# FlightLogger.net
KiCad netlist of a schematic drawn in Altium Designer
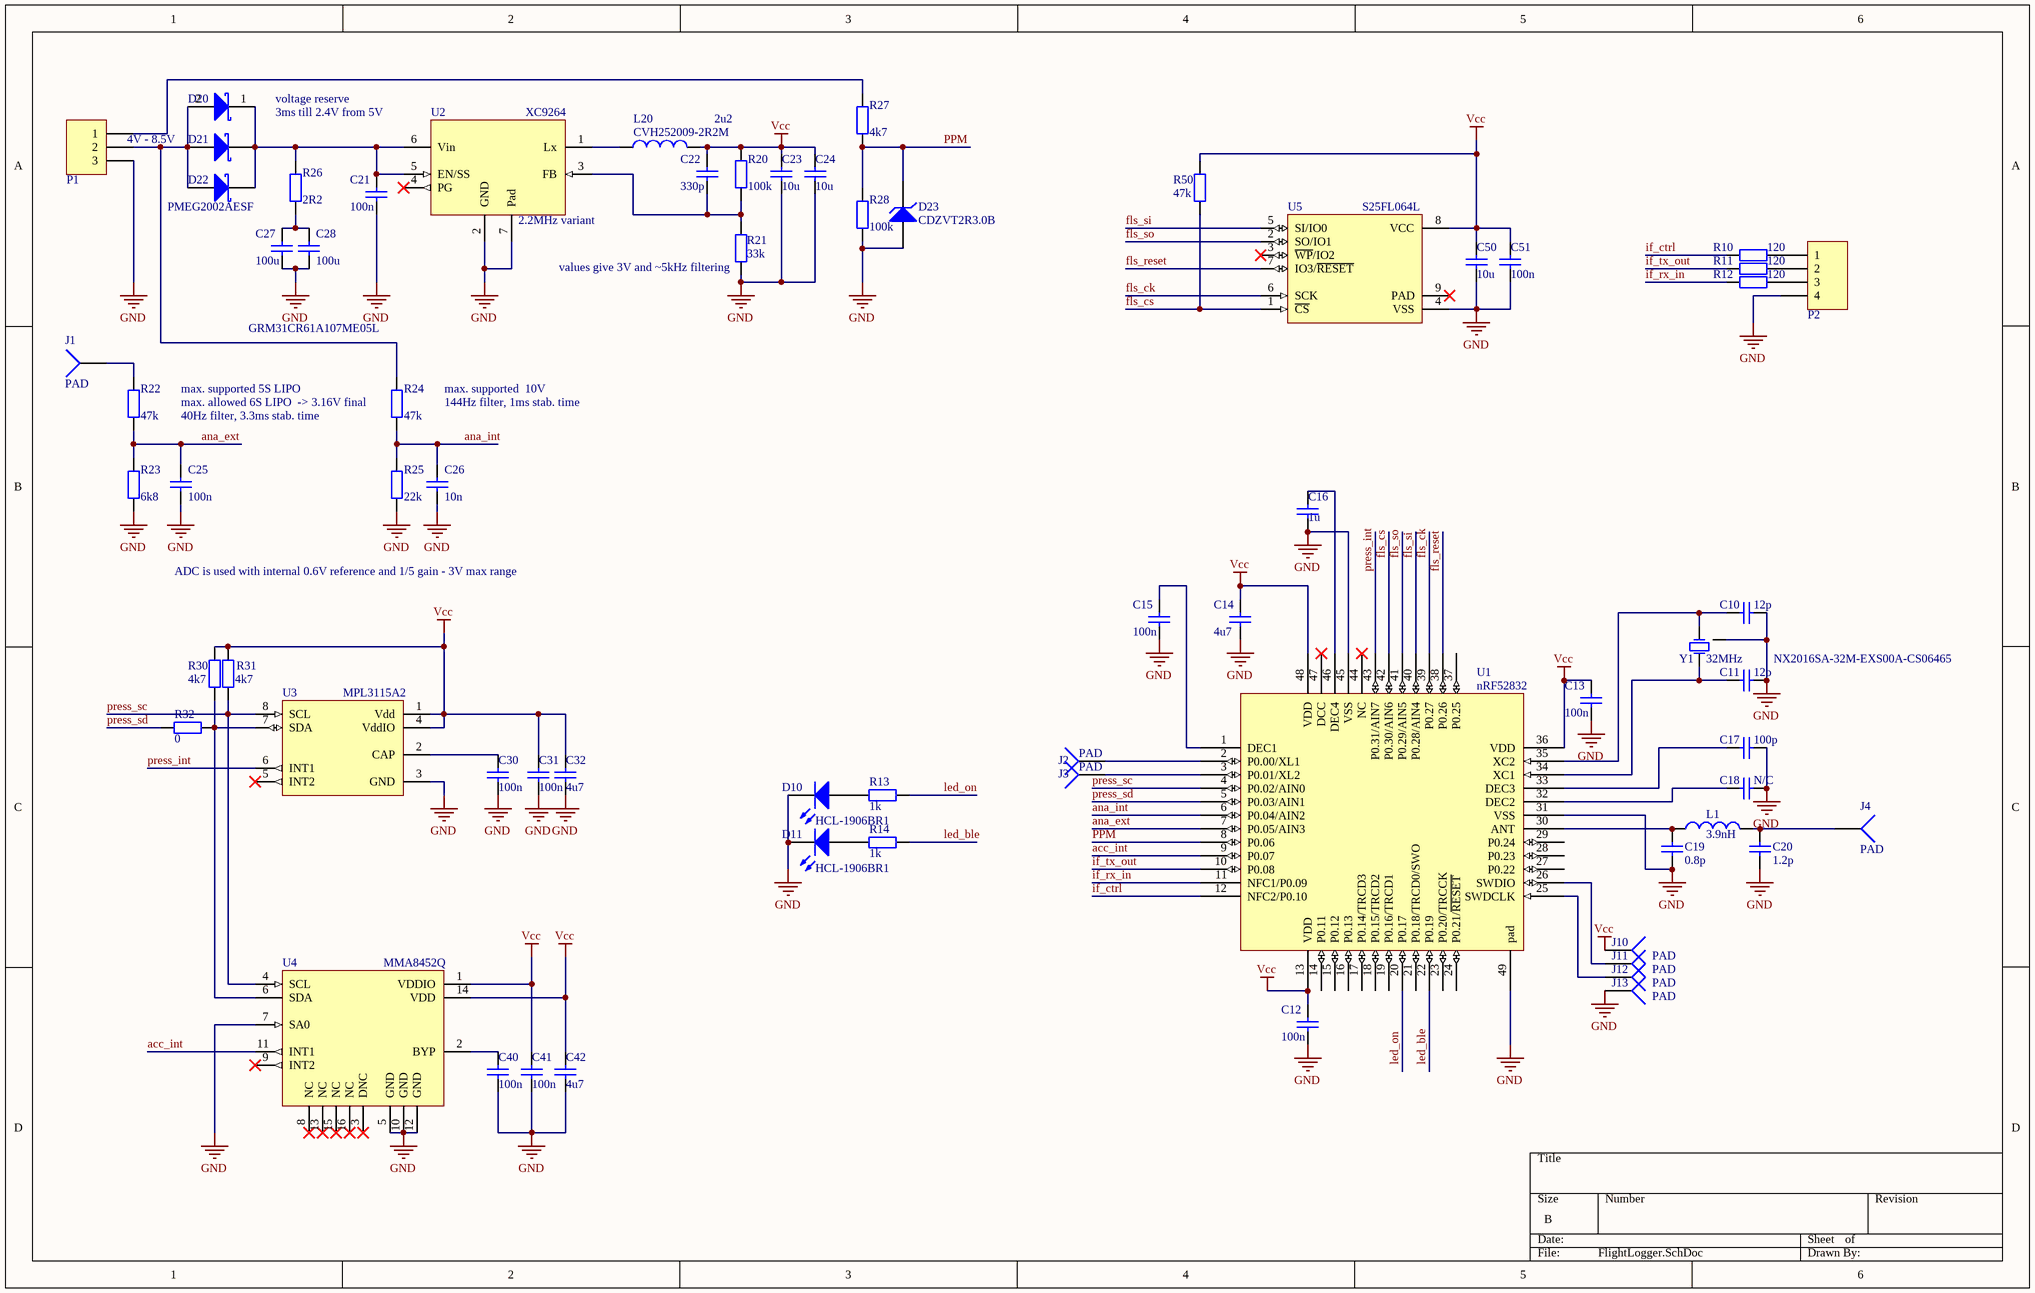
[diagram p0: FlightLogger.SchDoc]

(export (version "E")
  (design (tool "Eeschema 10.0.6"))
  (components
    (comp (ref "C10")
      (value "12p")
      (footprint "0402_cap")
      (description "Capacitor")
      (fields (field (name "PUBLISHER") "Altium Limited"))
      (libsource (lib "MyLib") (part "CAP"))
    )
    (comp (ref "C11")
      (value "12p")
      (footprint "0402_cap")
      (description "Capacitor")
      (fields (field (name "PUBLISHER") "Altium Limited"))
      (libsource (lib "MyLib") (part "CAP"))
    )
    (comp (ref "C12")
      (value "100n")
      (footprint "0402_cap")
      (description "Capacitor")
      (fields (field (name "PUBLISHER") "Altium Limited"))
      (libsource (lib "MyLib") (part "CAP"))
    )
    (comp (ref "C13")
      (value "100n")
      (footprint "0402_cap")
      (description "Capacitor")
      (fields (field (name "PUBLISHER") "Altium Limited"))
      (libsource (lib "MyLib") (part "CAP"))
    )
    (comp (ref "C14")
      (value "4u7")
      (footprint "0402_cap")
      (description "Capacitor")
      (fields (field (name "PUBLISHER") "Altium Limited"))
      (libsource (lib "MyLib") (part "CAP"))
    )
    (comp (ref "C15")
      (value "100n")
      (footprint "0402_cap")
      (description "Capacitor")
      (fields (field (name "PUBLISHER") "Altium Limited"))
      (libsource (lib "MyLib") (part "CAP"))
    )
    (comp (ref "C16")
      (value "1u")
      (footprint "0402_cap")
      (description "Capacitor")
      (fields (field (name "PUBLISHER") "Altium Limited"))
      (libsource (lib "MyLib") (part "CAP"))
    )
    (comp (ref "C17")
      (value "100p")
      (footprint "0402_cap")
      (description "Capacitor")
      (fields (field (name "PUBLISHER") "Altium Limited"))
      (libsource (lib "MyLib") (part "CAP"))
    )
    (comp (ref "C18")
      (value "N/C")
      (footprint "0402_cap")
      (description "Capacitor")
      (fields (field (name "PUBLISHER") "Altium Limited"))
      (libsource (lib "MyLib") (part "CAP"))
    )
    (comp (ref "C19")
      (value "0.8p")
      (footprint "0402_cap")
      (description "Capacitor")
      (fields (field (name "PUBLISHER") "Altium Limited"))
      (libsource (lib "MyLib") (part "CAP"))
    )
    (comp (ref "C20")
      (value "1.2p")
      (footprint "0402_cap")
      (description "Capacitor")
      (fields (field (name "PUBLISHER") "Altium Limited"))
      (libsource (lib "MyLib") (part "CAP"))
    )
    (comp (ref "C21")
      (value "100n")
      (footprint "0402_cap")
      (description "Capacitor")
      (fields (field (name "PUBLISHER") "Altium Limited"))
      (libsource (lib "MyLib") (part "CAP"))
    )
    (comp (ref "C22")
      (value "330p")
      (footprint "0402_cap")
      (description "Capacitor")
      (fields (field (name "PUBLISHER") "Altium Limited"))
      (libsource (lib "MyLib") (part "CAP"))
    )
    (comp (ref "C23")
      (value "10u")
      (footprint "0402_cap")
      (description "Capacitor")
      (fields (field (name "PUBLISHER") "Altium Limited"))
      (libsource (lib "MyLib") (part "CAP"))
    )
    (comp (ref "C24")
      (value "10u")
      (footprint "0402_cap")
      (description "Capacitor")
      (fields (field (name "PUBLISHER") "Altium Limited"))
      (libsource (lib "MyLib") (part "CAP"))
    )
    (comp (ref "C25")
      (value "100n")
      (footprint "0402_cap")
      (description "Capacitor")
      (fields (field (name "PUBLISHER") "Altium Limited"))
      (libsource (lib "MyLib") (part "CAP"))
    )
    (comp (ref "C26")
      (value "10n")
      (footprint "0402_cap")
      (description "Capacitor")
      (fields (field (name "PUBLISHER") "Altium Limited"))
      (libsource (lib "MyLib") (part "CAP"))
    )
    (comp (ref "C27")
      (value "100u")
      (footprint "1206_cap")
      (description "Capacitor")
      (fields (field (name "PARTNO") "GRM31CR61A107ME05L") (field (name "PUBLISHER") "Altium Limited"))
      (libsource (lib "MyLib") (part "CAP"))
    )
    (comp (ref "C28")
      (value "100u")
      (footprint "1206_cap")
      (description "Capacitor")
      (fields (field (name "PARTNO") "GRM31CR61A107ME05L") (field (name "PUBLISHER") "Altium Limited"))
      (libsource (lib "MyLib") (part "CAP"))
    )
    (comp (ref "C30")
      (value "100n")
      (footprint "0402_cap")
      (description "Capacitor")
      (fields (field (name "PUBLISHER") "Altium Limited"))
      (libsource (lib "MyLib") (part "CAP"))
    )
    (comp (ref "C31")
      (value "100n")
      (footprint "0402_cap")
      (description "Capacitor")
      (fields (field (name "PUBLISHER") "Altium Limited"))
      (libsource (lib "MyLib") (part "CAP"))
    )
    (comp (ref "C32")
      (value "4u7")
      (footprint "0402_cap")
      (description "Capacitor")
      (fields (field (name "PUBLISHER") "Altium Limited"))
      (libsource (lib "MyLib") (part "CAP"))
    )
    (comp (ref "C40")
      (value "100n")
      (footprint "0402_cap")
      (description "Capacitor")
      (fields (field (name "PUBLISHER") "Altium Limited"))
      (libsource (lib "MyLib") (part "CAP"))
    )
    (comp (ref "C41")
      (value "100n")
      (footprint "0402_cap")
      (description "Capacitor")
      (fields (field (name "PUBLISHER") "Altium Limited"))
      (libsource (lib "MyLib") (part "CAP"))
    )
    (comp (ref "C42")
      (value "4u7")
      (footprint "0402_cap")
      (description "Capacitor")
      (fields (field (name "PUBLISHER") "Altium Limited"))
      (libsource (lib "MyLib") (part "CAP"))
    )
    (comp (ref "C50")
      (value "10u")
      (footprint "0402_cap")
      (description "Capacitor")
      (fields (field (name "PUBLISHER") "Altium Limited"))
      (libsource (lib "MyLib") (part "CAP"))
    )
    (comp (ref "C51")
      (value "100n")
      (footprint "0402_cap")
      (description "Capacitor")
      (fields (field (name "PUBLISHER") "Altium Limited"))
      (libsource (lib "MyLib") (part "CAP"))
    )
    (comp (ref "D10")
      (value "HCL-1906BR1")
      (footprint "0603_led_green")
      (description "Typical RED, GREEN, YELLOW, AMBER GaAs LED")
      (fields (field (name "PUBLISHER") "Altium Limited"))
      (libsource (lib "MyLib") (part "LED"))
    )
    (comp (ref "D11")
      (value "HCL-1906BR1")
      (footprint "0603_led_green")
      (description "Typical RED, GREEN, YELLOW, AMBER GaAs LED")
      (fields (field (name "PUBLISHER") "Altium Limited"))
      (libsource (lib "MyLib") (part "LED"))
    )
    (comp (ref "D20")
      (value "PMEG2002AESF")
      (footprint "SOD962_2")
      (description "Schottky Barrier Diode")
      (fields (field (name "PUBLISHER") "Altium Limited"))
      (libsource (lib "") (part "1PS76SB10_1"))
    )
    (comp (ref "D21")
      (value "PMEG2002AESF")
      (footprint "SOD962_2")
      (description "Schottky Barrier Diode")
      (fields (field (name "PUBLISHER") "Altium Limited"))
      (libsource (lib "Philips Discrete Diode - Schottky") (part "1PS76SB10"))
    )
    (comp (ref "D22")
      (value "PMEG2002AESF")
      (footprint "SOD962_2")
      (description "Schottky Barrier Diode")
      (fields (field (name "PUBLISHER") "Altium Limited"))
      (libsource (lib "Philips Discrete Diode - Schottky") (part "1PS76SB10"))
    )
    (comp (ref "D23")
      (value "CDZVT2R3.0B")
      (footprint "VMN2M")
      (description "Zener Diode")
      (fields (field (name "PUBLISHER") "Altium Limited"))
      (libsource (lib "Miscellaneous Devices") (part "D Zener"))
    )
    (comp (ref "J1")
      (value "PAD")
      (footprint "PAD_0.6x1mm")
      (description "Pad")
      (fields (field (name "PUBLISHER") "Altium Limited"))
      (libsource (lib "MyLib") (part "PAD"))
    )
    (comp (ref "J2")
      (value "PAD")
      (footprint "PAD_0.6x1mm")
      (description "Pad")
      (fields (field (name "PUBLISHER") "Altium Limited"))
      (libsource (lib "MyLib") (part "PAD"))
    )
    (comp (ref "J3")
      (value "PAD")
      (footprint "PAD_0.6x1mm")
      (description "Pad")
      (fields (field (name "PUBLISHER") "Altium Limited"))
      (libsource (lib "MyLib") (part "PAD"))
    )
    (comp (ref "J4")
      (value "PAD")
      (footprint "PAD_0.6x1mm")
      (description "Pad")
      (fields (field (name "PUBLISHER") "Altium Limited"))
      (libsource (lib "MyLib") (part "PAD"))
    )
    (comp (ref "J10")
      (value "PAD")
      (footprint "PAD_0.6x1mm")
      (description "Pad")
      (fields (field (name "PUBLISHER") "Altium Limited"))
      (libsource (lib "MyLib") (part "PAD"))
    )
    (comp (ref "J11")
      (value "PAD")
      (footprint "PAD_0.6x1mm")
      (description "Pad")
      (fields (field (name "PUBLISHER") "Altium Limited"))
      (libsource (lib "MyLib") (part "PAD"))
    )
    (comp (ref "J12")
      (value "PAD")
      (footprint "PAD_0.6x1mm")
      (description "Pad")
      (fields (field (name "PUBLISHER") "Altium Limited"))
      (libsource (lib "MyLib") (part "PAD"))
    )
    (comp (ref "J13")
      (value "PAD")
      (footprint "PAD_0.6x1mm")
      (description "Pad")
      (fields (field (name "PUBLISHER") "Altium Limited"))
      (libsource (lib "MyLib") (part "PAD"))
    )
    (comp (ref "L1")
      (value "3.9nH")
      (footprint "0402_res")
      (description "Inductor")
      (fields (field (name "PUBLISHER") "Altium Limited"))
      (libsource (lib "MyLib") (part "Inductor"))
    )
    (comp (ref "L20")
      (value "CVH252009-2R2M")
      (footprint "1008_Inductor")
      (description "Inductor")
      (fields (field (name "ALTIUM_VALUE") "2u2") (field (name "PUBLISHER") "Altium Limited"))
      (libsource (lib "MyLib") (part "Inductor"))
    )
    (comp (ref "P1")
      (value "Conn3")
      (footprint "HDR1X3")
      (description "3pin connection")
      (fields (field (name "PUBLISHER") "Altium Limited"))
      (libsource (lib "MyLib") (part "conn_3pin_1"))
    )
    (comp (ref "P2")
      (value "Conn4")
      (footprint "conn_4pin_1row_1mm")
      (description "4pin connection")
      (fields (field (name "PUBLISHER") "Altium Limited"))
      (libsource (lib "MyLib") (part "conn_4pin"))
    )
    (comp (ref "R10")
      (value "120")
      (footprint "0402_res")
      (description "Resistor")
      (fields (field (name "PUBLISHER") "Altium Limited"))
      (libsource (lib "") (part "RES_1"))
    )
    (comp (ref "R11")
      (value "120")
      (footprint "0402_res")
      (description "Resistor")
      (fields (field (name "PUBLISHER") "Altium Limited"))
      (libsource (lib "") (part "RES_1"))
    )
    (comp (ref "R12")
      (value "120")
      (footprint "0402_res")
      (description "Resistor")
      (fields (field (name "PUBLISHER") "Altium Limited"))
      (libsource (lib "") (part "RES_1"))
    )
    (comp (ref "R13")
      (value "1k")
      (footprint "0402_res")
      (description "Resistor")
      (fields (field (name "PUBLISHER") "Altium Limited"))
      (libsource (lib "") (part "RES_1"))
    )
    (comp (ref "R14")
      (value "1k")
      (footprint "0402_res")
      (description "Resistor")
      (fields (field (name "PUBLISHER") "Altium Limited"))
      (libsource (lib "") (part "RES_1"))
    )
    (comp (ref "R20")
      (value "100k")
      (footprint "0402_res")
      (description "Resistor")
      (fields (field (name "PUBLISHER") "Altium Limited"))
      (libsource (lib "MyLib") (part "RES"))
    )
    (comp (ref "R21")
      (value "33k")
      (footprint "0402_res")
      (description "Resistor")
      (fields (field (name "PUBLISHER") "Altium Limited"))
      (libsource (lib "") (part "RES_2"))
    )
    (comp (ref "R22")
      (value "47k")
      (footprint "0402_res")
      (description "Resistor")
      (fields (field (name "PUBLISHER") "Altium Limited"))
      (libsource (lib "MyLib") (part "RES"))
    )
    (comp (ref "R23")
      (value "6k8")
      (footprint "0402_res")
      (description "Resistor")
      (fields (field (name "PUBLISHER") "Altium Limited"))
      (libsource (lib "MyLib") (part "RES"))
    )
    (comp (ref "R24")
      (value "47k")
      (footprint "0402_res")
      (description "Resistor")
      (fields (field (name "PUBLISHER") "Altium Limited"))
      (libsource (lib "MyLib") (part "RES"))
    )
    (comp (ref "R25")
      (value "22k")
      (footprint "0402_res")
      (description "Resistor")
      (fields (field (name "PUBLISHER") "Altium Limited"))
      (libsource (lib "MyLib") (part "RES"))
    )
    (comp (ref "R26")
      (value "2R2")
      (footprint "0603_res")
      (description "Resistor")
      (fields (field (name "PUBLISHER") "Altium Limited"))
      (libsource (lib "MyLib") (part "RES"))
    )
    (comp (ref "R27")
      (value "4k7")
      (footprint "0402_res")
      (description "Resistor")
      (fields (field (name "PUBLISHER") "Altium Limited"))
      (libsource (lib "MyLib") (part "RES"))
    )
    (comp (ref "R28")
      (value "100k")
      (footprint "0402_res")
      (description "Resistor")
      (fields (field (name "PUBLISHER") "Altium Limited"))
      (libsource (lib "MyLib") (part "RES"))
    )
    (comp (ref "R30")
      (value "4k7")
      (footprint "0402_res")
      (description "Resistor")
      (fields (field (name "PUBLISHER") "Altium Limited"))
      (libsource (lib "MyLib") (part "RES"))
    )
    (comp (ref "R31")
      (value "4k7")
      (footprint "0402_res")
      (description "Resistor")
      (fields (field (name "PUBLISHER") "Altium Limited"))
      (libsource (lib "MyLib") (part "RES"))
    )
    (comp (ref "R32")
      (value "0")
      (footprint "0402_res")
      (description "Resistor")
      (fields (field (name "PUBLISHER") "Altium Limited"))
      (libsource (lib "") (part "RES_1"))
    )
    (comp (ref "R50")
      (value "47k")
      (footprint "0402_res")
      (description "Resistor")
      (fields (field (name "PUBLISHER") "Altium Limited"))
      (libsource (lib "MyLib") (part "RES"))
    )
    (comp (ref "U1")
      (value "nRF52832")
      (footprint "QFN48")
      (description "ARM Cortex M4  microcontroller with 2.4GHz radio")
      (libsource (lib "MyLib") (part "nRF52832"))
    )
    (comp (ref "U2")
      (value "XC9264")
      (footprint "USP-6C")
      (description "18V 0.5A step down DC-DC converter")
      (libsource (lib "MyLib") (part "XC9264"))
    )
    (comp (ref "U3")
      (value "MPL3115A2")
      (footprint "MPL3115A2")
      (description "Precision barometer sensor I2C")
      (fields (field (name "PUBLISHER") "Altium Limited"))
      (libsource (lib "MyLib") (part "MPL3115A2"))
    )
    (comp (ref "U4")
      (value "MMA8452Q")
      (footprint "QFN16SP")
      (description "3 axis accelerometer")
      (fields (field (name "PUBLISHER") "Altium Limited"))
      (libsource (lib "MyLib") (part "MMA8452Q"))
    )
    (comp (ref "U5")
      (value "S25FL064L")
      (footprint "USON8")
      (description "64Mbit NOR flash")
      (fields (field (name "PUBLISHER") "Altium Limited"))
      (libsource (lib "MyLib") (part "S25FL064L"))
    )
    (comp (ref "Y1")
      (value "32MHz")
      (footprint "Cristal_2_1.6_4pin")
      (description "Crystal Oscillator")
      (fields
        (field (name "PART.NO") "NX2016SA-32M-EXS00A-CS06465")
        (field (name "PUBLISHER") "Altium Limited")
      )
      (libsource (lib "MyLib") (part "XTAL"))
    )
  )
  (nets
    (net (code "1") (name "/PPM") (class "Default")
      (node (ref "D23") (pin "2") (pinfunction "K_2") (pintype "passive"))
      (node (ref "R27") (pin "2") (pinfunction "2_2") (pintype "passive"))
      (node (ref "R28") (pin "1") (pinfunction "1_1") (pintype "passive"))
      (node (ref "U1") (pin "8") (pinfunction "P0.06_8") (pintype "bidirectional"))
    )
    (net (code "2") (name "/acc_int") (class "Default")
      (node (ref "U1") (pin "9") (pinfunction "P0.07_9") (pintype "bidirectional"))
      (node (ref "U4") (pin "11") (pinfunction "INT1_11") (pintype "output"))
    )
    (net (code "3") (name "/ana_ext") (class "Default")
      (node (ref "C25") (pin "1") (pinfunction "1_1") (pintype "passive"))
      (node (ref "R22") (pin "2") (pinfunction "2_2") (pintype "passive"))
      (node (ref "R23") (pin "1") (pinfunction "1_1") (pintype "passive"))
      (node (ref "U1") (pin "7") (pinfunction "P0.05/AIN3_7") (pintype "bidirectional"))
    )
    (net (code "4") (name "/ana_int") (class "Default")
      (node (ref "C26") (pin "1") (pinfunction "1_1") (pintype "passive"))
      (node (ref "R24") (pin "2") (pinfunction "2_2") (pintype "passive"))
      (node (ref "R25") (pin "1") (pinfunction "1_1") (pintype "passive"))
      (node (ref "U1") (pin "6") (pinfunction "P0.04/AIN2_6") (pintype "bidirectional"))
    )
    (net (code "5") (name "/fls_ck") (class "Default")
      (node (ref "U1") (pin "39") (pinfunction "P0.27_39") (pintype "bidirectional"))
      (node (ref "U5") (pin "6") (pinfunction "SCK_6") (pintype "input"))
    )
    (net (code "6") (name "/fls_cs") (class "Default")
      (node (ref "R50") (pin "2") (pinfunction "2_2") (pintype "passive"))
      (node (ref "U1") (pin "42") (pinfunction "P0.30/AIN6_42") (pintype "bidirectional"))
      (node (ref "U5") (pin "1") (pinfunction "~{CS}_1") (pintype "input"))
    )
    (net (code "7") (name "/fls_reset") (class "Default")
      (node (ref "U1") (pin "38") (pinfunction "P0.26_38") (pintype "bidirectional"))
      (node (ref "U5") (pin "7") (pinfunction "IO3/~{RESET}_7") (pintype "bidirectional"))
    )
    (net (code "8") (name "/fls_si") (class "Default")
      (node (ref "U1") (pin "40") (pinfunction "P0.28/AIN4_40") (pintype "bidirectional"))
      (node (ref "U5") (pin "5") (pinfunction "SI/IO0_5") (pintype "bidirectional"))
    )
    (net (code "9") (name "/fls_so") (class "Default")
      (node (ref "U1") (pin "41") (pinfunction "P0.29/AIN5_41") (pintype "bidirectional"))
      (node (ref "U5") (pin "2") (pinfunction "SO/IO1_2") (pintype "bidirectional"))
    )
    (net (code "10") (name "/if_ctrl") (class "Default")
      (node (ref "R10") (pin "2") (pinfunction "2_2") (pintype "passive"))
      (node (ref "U1") (pin "12") (pinfunction "NFC2/P0.10_12") (pintype "tri_state"))
    )
    (net (code "11") (name "/if_rx_in") (class "Default")
      (node (ref "R12") (pin "2") (pinfunction "2_2") (pintype "passive"))
      (node (ref "U1") (pin "11") (pinfunction "NFC1/P0.09_11") (pintype "tri_state"))
    )
    (net (code "12") (name "/if_tx_out") (class "Default")
      (node (ref "R11") (pin "2") (pinfunction "2_2") (pintype "passive"))
      (node (ref "U1") (pin "10") (pinfunction "P0.08_10") (pintype "bidirectional"))
    )
    (net (code "13") (name "/led_ble") (class "Default")
      (node (ref "R14") (pin "1") (pinfunction "1_1") (pintype "passive"))
      (node (ref "U1") (pin "22") (pinfunction "P0.19_22") (pintype "bidirectional"))
    )
    (net (code "14") (name "/led_on") (class "Default")
      (node (ref "R13") (pin "1") (pinfunction "1_1") (pintype "passive"))
      (node (ref "U1") (pin "20") (pinfunction "P0.17_20") (pintype "bidirectional"))
    )
    (net (code "15") (name "/press_int") (class "Default")
      (node (ref "U1") (pin "43") (pinfunction "P0.31/AIN7_43") (pintype "bidirectional"))
      (node (ref "U3") (pin "6") (pinfunction "INT1_6") (pintype "output"))
    )
    (net (code "16") (name "/press_sc") (class "Default")
      (node (ref "R31") (pin "2") (pinfunction "2_2") (pintype "passive"))
      (node (ref "U1") (pin "4") (pinfunction "P0.02/AIN0_4") (pintype "bidirectional"))
      (node (ref "U3") (pin "8") (pinfunction "SCL_8") (pintype "input"))
      (node (ref "U4") (pin "4") (pinfunction "SCL_4") (pintype "input"))
    )
    (net (code "17") (name "/press_sd") (class "Default")
      (node (ref "R32") (pin "2") (pinfunction "2_2") (pintype "passive"))
      (node (ref "U1") (pin "5") (pinfunction "P0.03/AIN1_5") (pintype "bidirectional"))
    )
    (net (code "18") (name "GND") (class "Default")
      (node (ref "C10") (pin "1") (pinfunction "1_1") (pintype "passive"))
      (node (ref "C11") (pin "1") (pinfunction "1_1") (pintype "passive"))
      (node (ref "C12") (pin "2") (pinfunction "2_2") (pintype "passive"))
      (node (ref "C13") (pin "2") (pinfunction "2_2") (pintype "passive"))
      (node (ref "C14") (pin "2") (pinfunction "2_2") (pintype "passive"))
      (node (ref "C15") (pin "2") (pinfunction "2_2") (pintype "passive"))
      (node (ref "C16") (pin "2") (pinfunction "2_2") (pintype "passive"))
      (node (ref "C17") (pin "1") (pinfunction "1_1") (pintype "passive"))
      (node (ref "C18") (pin "1") (pinfunction "1_1") (pintype "passive"))
      (node (ref "C19") (pin "1") (pinfunction "1_1") (pintype "passive"))
      (node (ref "C20") (pin "1") (pinfunction "1_1") (pintype "passive"))
      (node (ref "C21") (pin "2") (pinfunction "2_2") (pintype "passive"))
      (node (ref "C23") (pin "2") (pinfunction "2_2") (pintype "passive"))
      (node (ref "C24") (pin "2") (pinfunction "2_2") (pintype "passive"))
      (node (ref "C25") (pin "2") (pinfunction "2_2") (pintype "passive"))
      (node (ref "C26") (pin "2") (pinfunction "2_2") (pintype "passive"))
      (node (ref "C27") (pin "1") (pinfunction "1_1") (pintype "passive"))
      (node (ref "C28") (pin "1") (pinfunction "1_1") (pintype "passive"))
      (node (ref "C30") (pin "1") (pinfunction "1_1") (pintype "passive"))
      (node (ref "C31") (pin "1") (pinfunction "1_1") (pintype "passive"))
      (node (ref "C32") (pin "1") (pinfunction "1_1") (pintype "passive"))
      (node (ref "C40") (pin "1") (pinfunction "1_1") (pintype "passive"))
      (node (ref "C41") (pin "1") (pinfunction "1_1") (pintype "passive"))
      (node (ref "C42") (pin "1") (pinfunction "1_1") (pintype "passive"))
      (node (ref "C50") (pin "1") (pinfunction "1_1") (pintype "passive"))
      (node (ref "C51") (pin "1") (pinfunction "1_1") (pintype "passive"))
      (node (ref "D10") (pin "2") (pinfunction "K_2") (pintype "passive"))
      (node (ref "D11") (pin "2") (pinfunction "K_2") (pintype "passive"))
      (node (ref "D23") (pin "1") (pinfunction "A_1") (pintype "passive"))
      (node (ref "J13") (pin "1") (pinfunction "1_1") (pintype "passive"))
      (node (ref "P1") (pin "3") (pinfunction "3_3") (pintype "passive"))
      (node (ref "P2") (pin "4") (pinfunction "4_4") (pintype "passive"))
      (node (ref "R21") (pin "1") (pinfunction "1_1") (pintype "passive"))
      (node (ref "R23") (pin "2") (pinfunction "2_2") (pintype "passive"))
      (node (ref "R25") (pin "2") (pinfunction "2_2") (pintype "passive"))
      (node (ref "R28") (pin "2") (pinfunction "2_2") (pintype "passive"))
      (node (ref "U1") (pin "31") (pinfunction "VSS_31") (pintype "power_in"))
      (node (ref "U1") (pin "45") (pinfunction "VSS_45") (pintype "power_in"))
      (node (ref "U1") (pin "49") (pinfunction "pad_49") (pintype "power_in"))
      (node (ref "U2") (pin "2") (pinfunction "GND_2") (pintype "power_in"))
      (node (ref "U2") (pin "7") (pinfunction "Pad_7") (pintype "passive"))
      (node (ref "U3") (pin "3") (pinfunction "GND_3") (pintype "power_in"))
      (node (ref "U4") (pin "10") (pinfunction "GND_10") (pintype "power_in"))
      (node (ref "U4") (pin "12") (pinfunction "GND_12") (pintype "power_in"))
      (node (ref "U4") (pin "5") (pinfunction "GND_5") (pintype "power_in"))
      (node (ref "U4") (pin "7") (pinfunction "SA0_7") (pintype "input"))
      (node (ref "U5") (pin "4") (pinfunction "VSS_4") (pintype "power_in"))
      (node (ref "Y1") (pin "2") (pinfunction "GND_2") (pintype "passive"))
    )
    (net (code "19") (name "Net-(C20-Pad2)") (class "Default")
      (node (ref "C20") (pin "2") (pinfunction "2_2") (pintype "passive"))
      (node (ref "J4") (pin "1") (pinfunction "1_1") (pintype "passive"))
      (node (ref "L1") (pin "2") (pinfunction "2_2") (pintype "passive"))
    )
    (net (code "20") (name "Net-(C27-Pad2)") (class "Default")
      (node (ref "C27") (pin "2") (pinfunction "2_2") (pintype "passive"))
      (node (ref "C28") (pin "2") (pinfunction "2_2") (pintype "passive"))
      (node (ref "R26") (pin "2") (pinfunction "2_2") (pintype "passive"))
    )
    (net (code "21") (name "Net-(D10-A)") (class "Default")
      (node (ref "D10") (pin "1") (pinfunction "A_1") (pintype "passive"))
      (node (ref "R13") (pin "2") (pinfunction "2_2") (pintype "passive"))
    )
    (net (code "22") (name "Net-(D11-A)") (class "Default")
      (node (ref "D11") (pin "1") (pinfunction "A_1") (pintype "passive"))
      (node (ref "R14") (pin "2") (pinfunction "2_2") (pintype "passive"))
    )
    (net (code "23") (name "Net-(D20-A)") (class "Default")
      (node (ref "D20") (pin "2") (pinfunction "A_2") (pintype "passive"))
      (node (ref "D21") (pin "2") (pinfunction "A_2") (pintype "passive"))
      (node (ref "D22") (pin "2") (pinfunction "A_2") (pintype "passive"))
      (node (ref "P1") (pin "2") (pinfunction "2_2") (pintype "passive"))
      (node (ref "R24") (pin "1") (pinfunction "1_1") (pintype "passive"))
    )
    (net (code "24") (name "Net-(D20-K)") (class "Default")
      (node (ref "C21") (pin "1") (pinfunction "1_1") (pintype "passive"))
      (node (ref "D20") (pin "1") (pinfunction "K_1") (pintype "passive"))
      (node (ref "D21") (pin "1") (pinfunction "K_1") (pintype "passive"))
      (node (ref "D22") (pin "1") (pinfunction "K_1") (pintype "passive"))
      (node (ref "R26") (pin "1") (pinfunction "1_1") (pintype "passive"))
      (node (ref "U2") (pin "5") (pinfunction "EN/SS_5") (pintype "input"))
      (node (ref "U2") (pin "6") (pinfunction "Vin_6") (pintype "power_in"))
    )
    (net (code "25") (name "Net-(J1-Pad1)") (class "Default")
      (node (ref "J1") (pin "1") (pinfunction "1_1") (pintype "passive"))
      (node (ref "R22") (pin "1") (pinfunction "1_1") (pintype "passive"))
    )
    (net (code "26") (name "Net-(P1-Pad1)") (class "Default")
      (node (ref "P1") (pin "1") (pinfunction "1_1") (pintype "passive"))
      (node (ref "R27") (pin "1") (pinfunction "1_1") (pintype "passive"))
    )
    (net (code "27") (name "Net-(P2-Pad1)") (class "Default")
      (node (ref "P2") (pin "1") (pinfunction "1_1") (pintype "passive"))
      (node (ref "R10") (pin "1") (pinfunction "1_1") (pintype "passive"))
    )
    (net (code "28") (name "Net-(P2-Pad2)") (class "Default")
      (node (ref "P2") (pin "2") (pinfunction "2_2") (pintype "passive"))
      (node (ref "R11") (pin "1") (pinfunction "1_1") (pintype "passive"))
    )
    (net (code "29") (name "Net-(P2-Pad3)") (class "Default")
      (node (ref "P2") (pin "3") (pinfunction "3_3") (pintype "passive"))
      (node (ref "R12") (pin "1") (pinfunction "1_1") (pintype "passive"))
    )
    (net (code "30") (name "Net-(U1-ANT)") (class "Default")
      (node (ref "C19") (pin "2") (pinfunction "2_2") (pintype "passive"))
      (node (ref "L1") (pin "1") (pinfunction "1_1") (pintype "passive"))
      (node (ref "U1") (pin "30") (pinfunction "ANT_30") (pintype "tri_state"))
    )
    (net (code "31") (name "Net-(U1-DEC1)") (class "Default")
      (node (ref "C15") (pin "1") (pinfunction "1_1") (pintype "passive"))
      (node (ref "U1") (pin "1") (pinfunction "DEC1_1") (pintype "power_in"))
    )
    (net (code "32") (name "Net-(U1-DEC2)") (class "Default")
      (node (ref "C18") (pin "2") (pinfunction "2_2") (pintype "passive"))
      (node (ref "U1") (pin "32") (pinfunction "DEC2_32") (pintype "power_in"))
    )
    (net (code "33") (name "Net-(U1-DEC3)") (class "Default")
      (node (ref "C17") (pin "2") (pinfunction "2_2") (pintype "passive"))
      (node (ref "U1") (pin "33") (pinfunction "DEC3_33") (pintype "power_in"))
    )
    (net (code "34") (name "Net-(U1-DEC4)") (class "Default")
      (node (ref "C16") (pin "1") (pinfunction "1_1") (pintype "passive"))
      (node (ref "U1") (pin "46") (pinfunction "DEC4_46") (pintype "power_in"))
    )
    (net (code "35") (name "Net-(U1-P0.00{slash}XL1)") (class "Default")
      (node (ref "J2") (pin "1") (pinfunction "1_1") (pintype "passive"))
      (node (ref "U1") (pin "2") (pinfunction "P0.00/XL1_2") (pintype "bidirectional"))
    )
    (net (code "36") (name "Net-(U1-P0.01{slash}XL2)") (class "Default")
      (node (ref "J3") (pin "1") (pinfunction "1_1") (pintype "passive"))
      (node (ref "U1") (pin "3") (pinfunction "P0.01/XL2_3") (pintype "bidirectional"))
    )
    (net (code "37") (name "Net-(U1-SWDCLK)") (class "Default")
      (node (ref "J12") (pin "1") (pinfunction "1_1") (pintype "passive"))
      (node (ref "U1") (pin "25") (pinfunction "SWDCLK_25") (pintype "input"))
    )
    (net (code "38") (name "Net-(U1-SWDIO)") (class "Default")
      (node (ref "J11") (pin "1") (pinfunction "1_1") (pintype "passive"))
      (node (ref "U1") (pin "26") (pinfunction "SWDIO_26") (pintype "bidirectional"))
    )
    (net (code "39") (name "Net-(U1-XC1)") (class "Default")
      (node (ref "C11") (pin "2") (pinfunction "2_2") (pintype "passive"))
      (node (ref "U1") (pin "34") (pinfunction "XC1_34") (pintype "input"))
      (node (ref "Y1") (pin "3") (pinfunction "OSC2_3") (pintype "passive"))
    )
    (net (code "40") (name "Net-(U1-XC2)") (class "Default")
      (node (ref "C10") (pin "2") (pinfunction "2_2") (pintype "passive"))
      (node (ref "U1") (pin "35") (pinfunction "XC2_35") (pintype "input"))
      (node (ref "Y1") (pin "1") (pinfunction "OSC1_1") (pintype "passive"))
    )
    (net (code "41") (name "Net-(U2-FB)") (class "Default")
      (node (ref "C22") (pin "2") (pinfunction "2_2") (pintype "passive"))
      (node (ref "R20") (pin "2") (pinfunction "2_2") (pintype "passive"))
      (node (ref "R21") (pin "2") (pinfunction "2_2") (pintype "passive"))
      (node (ref "U2") (pin "3") (pinfunction "FB_3") (pintype "input"))
    )
    (net (code "42") (name "Net-(U2-Lx)") (class "Default")
      (node (ref "L20") (pin "1") (pinfunction "1_1") (pintype "passive"))
      (node (ref "U2") (pin "1") (pinfunction "Lx_1") (pintype "power_in"))
    )
    (net (code "43") (name "Net-(U3-CAP)") (class "Default")
      (node (ref "C30") (pin "2") (pinfunction "2_2") (pintype "passive"))
      (node (ref "U3") (pin "2") (pinfunction "CAP_2") (pintype "passive"))
    )
    (net (code "44") (name "Net-(U3-SDA)") (class "Default")
      (node (ref "R30") (pin "2") (pinfunction "2_2") (pintype "passive"))
      (node (ref "R32") (pin "1") (pinfunction "1_1") (pintype "passive"))
      (node (ref "U3") (pin "7") (pinfunction "SDA_7") (pintype "bidirectional"))
      (node (ref "U4") (pin "6") (pinfunction "SDA_6") (pintype "open_collector"))
    )
    (net (code "45") (name "Net-(U4-BYP)") (class "Default")
      (node (ref "C40") (pin "2") (pinfunction "2_2") (pintype "passive"))
      (node (ref "U4") (pin "2") (pinfunction "BYP_2") (pintype "passive"))
    )
    (net (code "46") (name "Vcc") (class "Default")
      (node (ref "C12") (pin "1") (pinfunction "1_1") (pintype "passive"))
      (node (ref "C13") (pin "1") (pinfunction "1_1") (pintype "passive"))
      (node (ref "C14") (pin "1") (pinfunction "1_1") (pintype "passive"))
      (node (ref "C22") (pin "1") (pinfunction "1_1") (pintype "passive"))
      (node (ref "C23") (pin "1") (pinfunction "1_1") (pintype "passive"))
      (node (ref "C24") (pin "1") (pinfunction "1_1") (pintype "passive"))
      (node (ref "C31") (pin "2") (pinfunction "2_2") (pintype "passive"))
      (node (ref "C32") (pin "2") (pinfunction "2_2") (pintype "passive"))
      (node (ref "C41") (pin "2") (pinfunction "2_2") (pintype "passive"))
      (node (ref "C42") (pin "2") (pinfunction "2_2") (pintype "passive"))
      (node (ref "C50") (pin "2") (pinfunction "2_2") (pintype "passive"))
      (node (ref "C51") (pin "2") (pinfunction "2_2") (pintype "passive"))
      (node (ref "J10") (pin "1") (pinfunction "1_1") (pintype "passive"))
      (node (ref "L20") (pin "2") (pinfunction "2_2") (pintype "passive"))
      (node (ref "R20") (pin "1") (pinfunction "1_1") (pintype "passive"))
      (node (ref "R30") (pin "1") (pinfunction "1_1") (pintype "passive"))
      (node (ref "R31") (pin "1") (pinfunction "1_1") (pintype "passive"))
      (node (ref "R50") (pin "1") (pinfunction "1_1") (pintype "passive"))
      (node (ref "U1") (pin "13") (pinfunction "VDD_13") (pintype "power_in"))
      (node (ref "U1") (pin "36") (pinfunction "VDD_36") (pintype "power_in"))
      (node (ref "U1") (pin "48") (pinfunction "VDD_48") (pintype "power_in"))
      (node (ref "U3") (pin "1") (pinfunction "Vdd_1") (pintype "power_in"))
      (node (ref "U3") (pin "4") (pinfunction "VddIO_4") (pintype "power_in"))
      (node (ref "U4") (pin "1") (pinfunction "VDDIO_1") (pintype "power_in"))
      (node (ref "U4") (pin "14") (pinfunction "VDD_14") (pintype "power_in"))
      (node (ref "U5") (pin "8") (pinfunction "VCC_8") (pintype "power_in"))
    )
    (net (code "47") (name "unconnected-(U1-DCC-Pad47)") (class "Default")
      (node (ref "U1") (pin "47") (pinfunction "DCC_47") (pintype "power_in+no_connect"))
    )
    (net (code "48") (name "unconnected-(U1-NC-Pad44)") (class "Default")
      (node (ref "U1") (pin "44") (pinfunction "NC_44") (pintype "passive+no_connect"))
    )
    (net (code "49") (name "unconnected-(U1-P0.11-Pad14)") (class "Default")
      (node (ref "U1") (pin "14") (pinfunction "P0.11_14") (pintype "bidirectional"))
    )
    (net (code "50") (name "unconnected-(U1-P0.12-Pad15)") (class "Default")
      (node (ref "U1") (pin "15") (pinfunction "P0.12_15") (pintype "bidirectional"))
    )
    (net (code "51") (name "unconnected-(U1-P0.13-Pad16)") (class "Default")
      (node (ref "U1") (pin "16") (pinfunction "P0.13_16") (pintype "bidirectional"))
    )
    (net (code "52") (name "unconnected-(U1-P0.14{slash}TRCD3-Pad17)") (class "Default")
      (node (ref "U1") (pin "17") (pinfunction "P0.14/TRCD3_17") (pintype "bidirectional"))
    )
    (net (code "53") (name "unconnected-(U1-P0.15{slash}TRCD2-Pad18)") (class "Default")
      (node (ref "U1") (pin "18") (pinfunction "P0.15/TRCD2_18") (pintype "bidirectional"))
    )
    (net (code "54") (name "unconnected-(U1-P0.16{slash}TRCD1-Pad19)") (class "Default")
      (node (ref "U1") (pin "19") (pinfunction "P0.16/TRCD1_19") (pintype "bidirectional"))
    )
    (net (code "55") (name "unconnected-(U1-P0.18{slash}TRCD0{slash}SWO-Pad21)") (class "Default")
      (node (ref "U1") (pin "21") (pinfunction "P0.18/TRCD0/SWO_21") (pintype "bidirectional"))
    )
    (net (code "56") (name "unconnected-(U1-P0.20{slash}TRCCK-Pad23)") (class "Default")
      (node (ref "U1") (pin "23") (pinfunction "P0.20/TRCCK_23") (pintype "bidirectional"))
    )
    (net (code "57") (name "unconnected-(U1-P0.21{slash}~{RESET}-Pad24)") (class "Default")
      (node (ref "U1") (pin "24") (pinfunction "P0.21/~{RESET}_24") (pintype "bidirectional"))
    )
    (net (code "58") (name "unconnected-(U1-P0.22-Pad27)") (class "Default")
      (node (ref "U1") (pin "27") (pinfunction "P0.22_27") (pintype "bidirectional"))
    )
    (net (code "59") (name "unconnected-(U1-P0.23-Pad28)") (class "Default")
      (node (ref "U1") (pin "28") (pinfunction "P0.23_28") (pintype "bidirectional"))
    )
    (net (code "60") (name "unconnected-(U1-P0.24-Pad29)") (class "Default")
      (node (ref "U1") (pin "29") (pinfunction "P0.24_29") (pintype "bidirectional"))
    )
    (net (code "61") (name "unconnected-(U1-P0.25-Pad37)") (class "Default")
      (node (ref "U1") (pin "37") (pinfunction "P0.25_37") (pintype "bidirectional"))
    )
    (net (code "62") (name "unconnected-(U2-PG-Pad4)") (class "Default")
      (node (ref "U2") (pin "4") (pinfunction "PG_4") (pintype "output+no_connect"))
    )
    (net (code "63") (name "unconnected-(U3-INT2-Pad5)") (class "Default")
      (node (ref "U3") (pin "5") (pinfunction "INT2_5") (pintype "output+no_connect"))
    )
    (net (code "64") (name "unconnected-(U4-DNC-Pad3)") (class "Default")
      (node (ref "U4") (pin "3") (pinfunction "DNC_3") (pintype "passive+no_connect"))
    )
    (net (code "65") (name "unconnected-(U4-INT2-Pad9)") (class "Default")
      (node (ref "U4") (pin "9") (pinfunction "INT2_9") (pintype "output+no_connect"))
    )
    (net (code "66") (name "unconnected-(U4-NC-Pad8)") (class "Default")
      (node (ref "U4") (pin "8") (pinfunction "NC_8") (pintype "passive+no_connect"))
    )
    (net (code "67") (name "unconnected-(U4-NC-Pad13)") (class "Default")
      (node (ref "U4") (pin "13") (pinfunction "NC_13") (pintype "passive+no_connect"))
    )
    (net (code "68") (name "unconnected-(U4-NC-Pad15)") (class "Default")
      (node (ref "U4") (pin "15") (pinfunction "NC_15") (pintype "passive+no_connect"))
    )
    (net (code "69") (name "unconnected-(U4-NC-Pad16)") (class "Default")
      (node (ref "U4") (pin "16") (pinfunction "NC_16") (pintype "passive+no_connect"))
    )
    (net (code "70") (name "unconnected-(U5-PAD-Pad9)") (class "Default")
      (node (ref "U5") (pin "9") (pinfunction "PAD_9") (pintype "passive+no_connect"))
    )
    (net (code "71") (name "unconnected-(U5-~{WP}{slash}IO2-Pad3)") (class "Default")
      (node (ref "U5") (pin "3") (pinfunction "~{WP}/IO2_3") (pintype "bidirectional+no_connect"))
    )
  )
)
